# SeniorDesign_PowerBoard_Rev3.net
KiCad netlist of a schematic drawn in Altium Designer
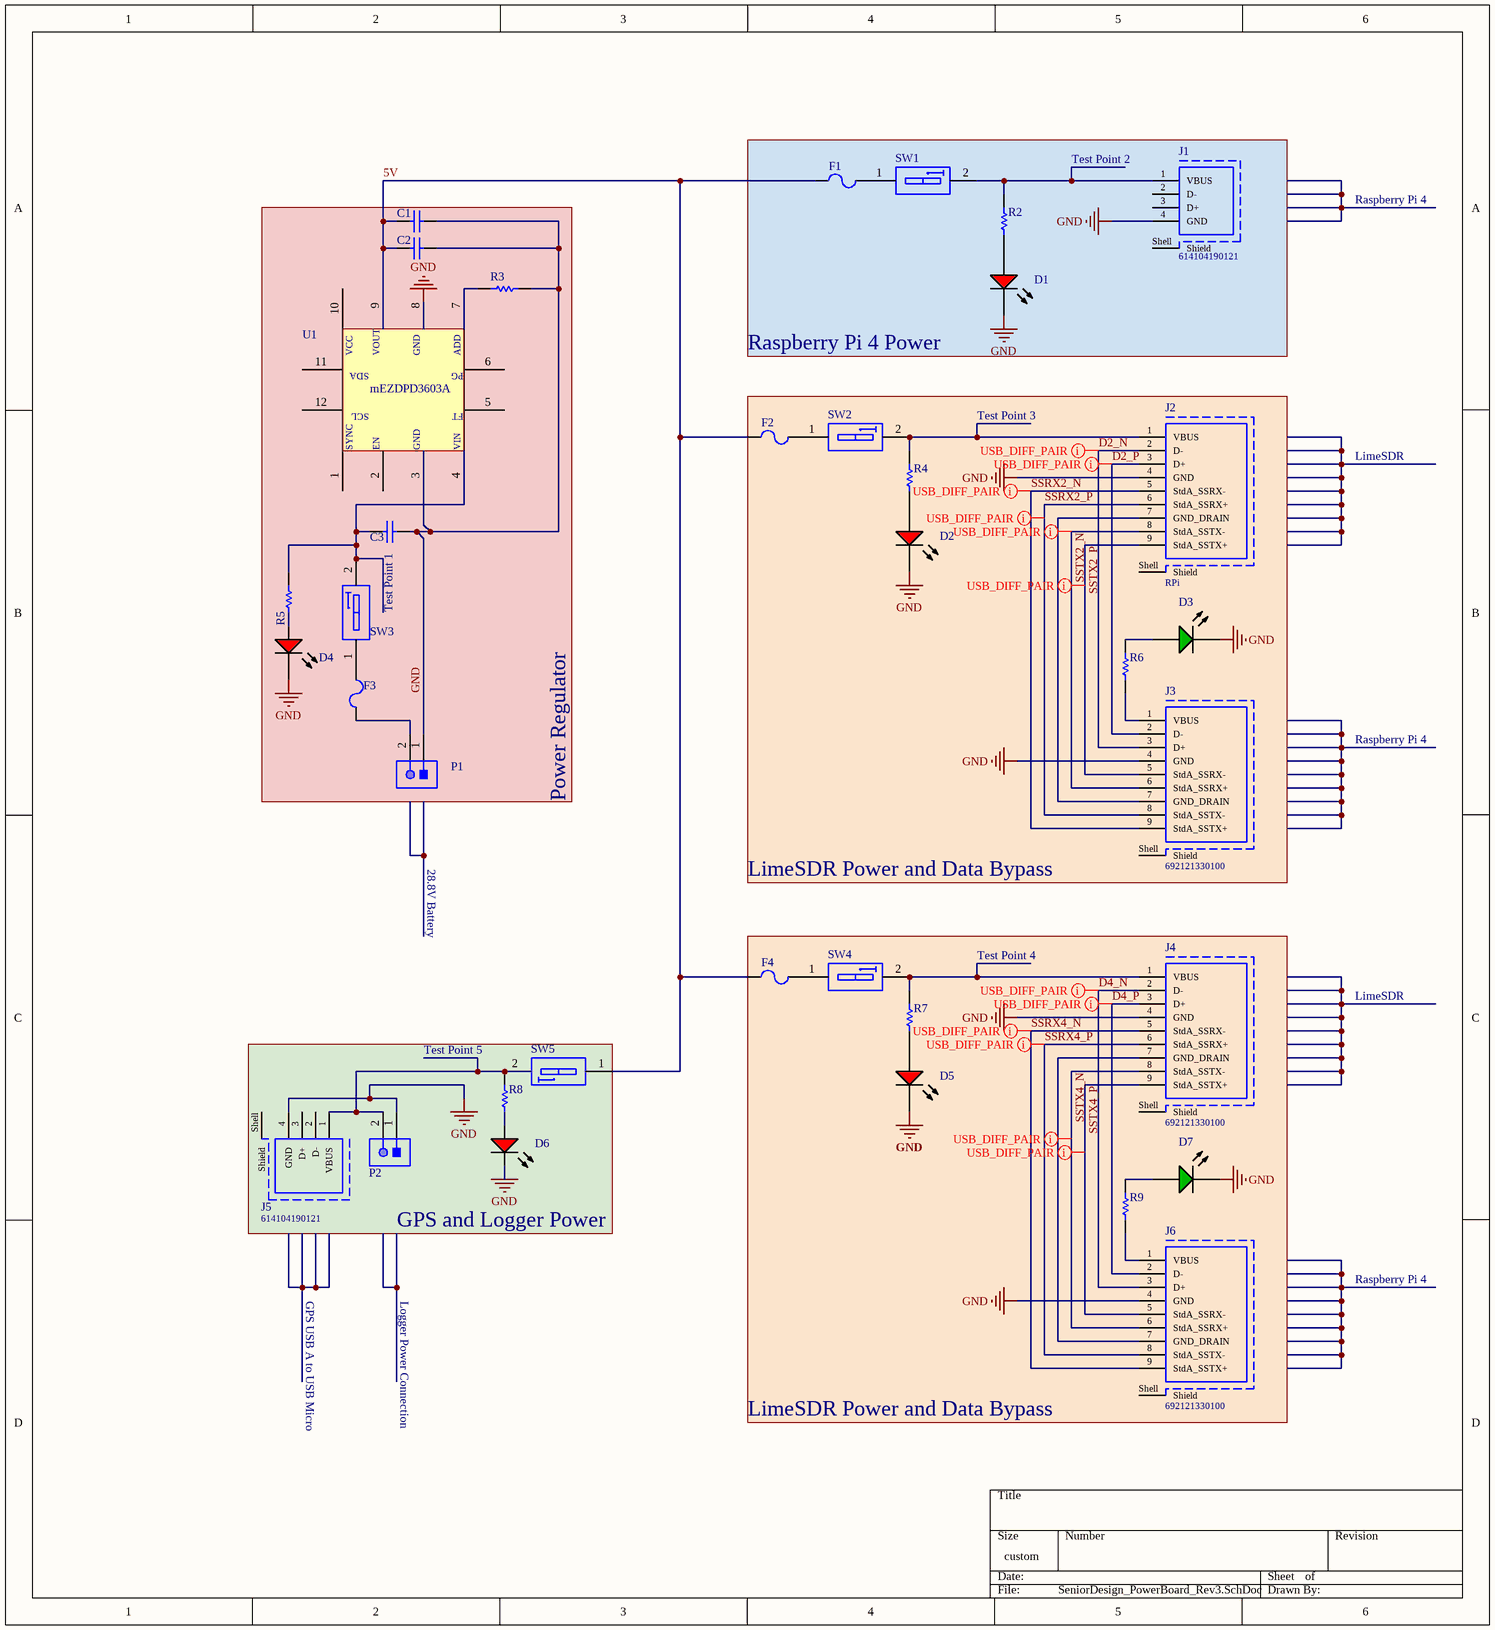
[diagram p0: SeniorDesign_PowerBoard_Rev3.SchDoc]

(export (version "E")
  (design (tool "Eeschema 10.0.6"))
  (components
    (comp (ref "C1")
      (value "GRM188R61A226ME15D")
      (footprint "CAPC1608X100X38LL20T18")
      (description "Chip Capacitor, 22 uF, +/- 20%, 10 V, -55 to 85 degC, 0603 (1608 Metric), RoHS, Tape and Reel")
      (fields (field (name "MANUFACTURER") "Murata") (field (name "TOLERANCE") "20%"))
      (libsource (lib "Altium Content Vault") (part "CAP-NP-2"))
    )
    (comp (ref "C2")
      (value "GRM188R61A226ME15D")
      (footprint "CAPC1608X100X38LL20T18")
      (description "Chip Capacitor, 22 uF, +/- 20%, 10 V, -55 to 85 degC, 0603 (1608 Metric), RoHS, Tape and Reel")
      (fields (field (name "MANUFACTURER") "Murata") (field (name "TOLERANCE") "20%"))
      (libsource (lib "Altium Content Vault") (part "CAP-NP-2"))
    )
    (comp (ref "C3")
      (value "GRM31CR71H475KA12L")
      (footprint "MURA-1206_H_1.8_M")
      (description "CAP, Ceramic, 4.7 uF, 10%, 50 V, 1206, RoHS, Tape and Reel")
      (fields (field (name "MANUFACTURER") "Murata"))
      (libsource (lib "Altium Content Vault") (part "CAP-NP-2"))
    )
    (comp (ref "D1")
      (value "HSMH-C150")
      (footprint "AVAG-HSMX-C150_V")
      (description "LED Uni-Color Red, 65 mW, 25 mA, -40 to 85 degC, 2-Pin SMD, RoHS, Tape and Reel")
      (fields (field (name "MANUFACTURER") "Avago"))
      (libsource (lib "Altium Content Vault") (part "LED-RED-AK-2"))
    )
    (comp (ref "D2")
      (value "HSMH-C150")
      (footprint "AVAG-HSMX-C150_V")
      (description "LED Uni-Color Red, 65 mW, 25 mA, -40 to 85 degC, 2-Pin SMD, RoHS, Tape and Reel")
      (fields (field (name "MANUFACTURER") "Avago"))
      (libsource (lib "Altium Content Vault") (part "LED-RED-AK-2"))
    )
    (comp (ref "D3")
      (value "HSMG-C150")
      (footprint "AVAG-HSMX-C150_V")
      (description "Chip LED, Green, 65 mW, 25 mA, -40 to 85 degC, 2-Pin SMD, RoHS, Tape and Reel")
      (fields (field (name "MANUFACTURER") "Avago"))
      (libsource (lib "Altium Content Vault") (part "LED_GREEN_A1K2-2"))
    )
    (comp (ref "D4")
      (value "HSMH-C150")
      (footprint "AVAG-HSMX-C150_V")
      (description "LED Uni-Color Red, 65 mW, 25 mA, -40 to 85 degC, 2-Pin SMD, RoHS, Tape and Reel")
      (fields (field (name "MANUFACTURER") "Avago"))
      (libsource (lib "Altium Content Vault") (part "LED-RED-AK-2"))
    )
    (comp (ref "D5")
      (value "HSMH-C150")
      (footprint "AVAG-HSMX-C150_V")
      (description "LED Uni-Color Red, 65 mW, 25 mA, -40 to 85 degC, 2-Pin SMD, RoHS, Tape and Reel")
      (fields (field (name "MANUFACTURER") "Avago"))
      (libsource (lib "Altium Content Vault") (part "LED-RED-AK-2"))
    )
    (comp (ref "D6")
      (value "HSMH-C150")
      (footprint "AVAG-HSMX-C150_V")
      (description "LED Uni-Color Red, 65 mW, 25 mA, -40 to 85 degC, 2-Pin SMD, RoHS, Tape and Reel")
      (fields (field (name "MANUFACTURER") "Avago"))
      (libsource (lib "Altium Content Vault") (part "LED-RED-AK-2"))
    )
    (comp (ref "D7")
      (value "HSMG-C150")
      (footprint "AVAG-HSMX-C150_V")
      (description "Chip LED, Green, 65 mW, 25 mA, -40 to 85 degC, 2-Pin SMD, RoHS, Tape and Reel")
      (fields (field (name "MANUFACTURER") "Avago"))
      (libsource (lib "Altium Content Vault") (part "LED_GREEN_A1K2-2"))
    )
    (comp (ref "F1")
      (value "0263.500WRT1L")
      (footprint "LFUS-263-2_V1")
      (fields (field (name "MANUFACTURER") "Littelfuse"))
      (libsource (lib "Altium Content Vault") (part "LFUS-FUSE-2"))
    )
    (comp (ref "F2")
      (value "0263.500WRT1L")
      (footprint "LFUS-263-2_V1")
      (fields (field (name "MANUFACTURER") "Littelfuse"))
      (libsource (lib "Altium Content Vault") (part "LFUS-FUSE-2"))
    )
    (comp (ref "F3")
      (value "0263.500WRT1L")
      (footprint "LFUS-263-2_V1")
      (fields (field (name "MANUFACTURER") "Littelfuse"))
      (libsource (lib "Altium Content Vault") (part "LFUS-FUSE-2"))
    )
    (comp (ref "F4")
      (value "0263.500WRT1L")
      (footprint "LFUS-263-2_V1")
      (fields (field (name "MANUFACTURER") "Littelfuse"))
      (libsource (lib "Altium Content Vault") (part "LFUS-FUSE-2"))
    )
    (comp (ref "J1")
      (value "614104190121")
      (footprint "614104190121")
      (description "USB 2.0 Type A Receptacle WR-COM, Horizontal, THT, Short Type with Clips")
      (fields (field (name "MANUFACTURER") "Wurth Elektronik") (field (name "PUBLISHER") "WurthElektronik"))
      (libsource (lib "Altium Content Vault") (part "WE-USB-4-1SHLD"))
    )
    (comp (ref "J2")
      (value "RPi")
      (footprint "692121330100")
      (description "USB 3.0 Type A Receptacle WR-COM, Reverse Horizontal, SMT / THT, with Clips, with 1.75 mm Offset")
      (fields
        (field (name "MANUFACTURER") "Wurth Elektronik")
        (field (name "PART NUMBER") "692121330100")
        (field (name "PUBLISHER") "WurthElektronik")
      )
      (libsource (lib "Altium Content Vault") (part "WE-USB-9-1SHLD"))
    )
    (comp (ref "J3")
      (value "692121330100")
      (footprint "692121330100")
      (description "USB 3.0 Type A Receptacle WR-COM, Reverse Horizontal, SMT / THT, with Clips, with 1.75 mm Offset")
      (fields (field (name "MANUFACTURER") "Wurth Elektronik") (field (name "PUBLISHER") "WurthElektronik"))
      (libsource (lib "Altium Content Vault") (part "WE-USB-9-1SHLD"))
    )
    (comp (ref "J4")
      (value "692121330100")
      (footprint "692121330100")
      (description "USB 3.0 Type A Receptacle WR-COM, Reverse Horizontal, SMT / THT, with Clips, with 1.75 mm Offset")
      (fields (field (name "MANUFACTURER") "Wurth Elektronik") (field (name "PUBLISHER") "WurthElektronik"))
      (libsource (lib "Altium Content Vault") (part "WE-USB-9-1SHLD"))
    )
    (comp (ref "J5")
      (value "614104190121")
      (footprint "614104190121")
      (description "USB 2.0 Type A Receptacle WR-COM, Horizontal, THT, Short Type with Clips")
      (fields (field (name "MANUFACTURER") "Wurth Elektronik") (field (name "PUBLISHER") "WurthElektronik"))
      (libsource (lib "Altium Content Vault") (part "WE-USB-4-1SHLD"))
    )
    (comp (ref "J6")
      (value "692121330100")
      (footprint "692121330100")
      (description "USB 3.0 Type A Receptacle WR-COM, Reverse Horizontal, SMT / THT, with Clips, with 1.75 mm Offset")
      (fields (field (name "MANUFACTURER") "Wurth Elektronik") (field (name "PUBLISHER") "WurthElektronik"))
      (libsource (lib "Altium Content Vault") (part "WE-USB-9-1SHLD"))
    )
    (comp (ref "P1")
      (value "S2B-PH-K-S(LF)(SN)")
      (footprint "JST-S2B-PH-K-S_V")
      (fields (field (name "TOLERANCE") "20%"))
      (libsource (lib "Altium Content Vault") (part "CN-1P-M-R2"))
    )
    (comp (ref "P2")
      (value "S2B-PH-K-S(LF)(SN)")
      (footprint "JST-S2B-PH-K-S_V")
      (fields (field (name "TOLERANCE") "20%"))
      (libsource (lib "Altium Content Vault") (part "CN-1P-M-R2"))
    )
    (comp (ref "R2")
      (value "CRCW0402150RFKED")
      (footprint "RESC1005X40X25LL05T05")
      (fields (field (name "MANUFACTURER") "Vishay Dale"))
      (libsource (lib "Altium Content Vault") (part "RES"))
    )
    (comp (ref "R3")
      (value "ADD")
      (footprint "RESC2013X50X30LL20T20")
      (fields (field (name "MANUFACTURER") "Vishay Dale") (field (name "PART NUMBER") "CRCW08050000Z0EA"))
      (libsource (lib "Altium Content Vault") (part "RES"))
    )
    (comp (ref "R4")
      (value "CRCW0402150RFKED")
      (footprint "RESC1005X40X25LL05T05")
      (fields (field (name "MANUFACTURER") "Vishay Dale"))
      (libsource (lib "Altium Content Vault") (part "RES"))
    )
    (comp (ref "R5")
      (value "ERJ-8ENF1501V")
      (footprint "RESC3216X70X50LL05T20")
      (description "1k5 Ohm")
      (fields (field (name "MANUFACTURER") "Panasonic"))
      (libsource (lib "Altium Content Vault") (part "RES"))
    )
    (comp (ref "R6")
      (value "CRCW0402150RFKED")
      (footprint "RESC1005X40X25LL05T05")
      (fields (field (name "MANUFACTURER") "Vishay Dale"))
      (libsource (lib "Altium Content Vault") (part "RES"))
    )
    (comp (ref "R7")
      (value "CRCW0402150RFKED")
      (footprint "RESC1005X40X25LL05T05")
      (fields (field (name "MANUFACTURER") "Vishay Dale"))
      (libsource (lib "Altium Content Vault") (part "RES"))
    )
    (comp (ref "R8")
      (value "CRCW0402150RFKED")
      (footprint "RESC1005X40X25LL05T05")
      (fields (field (name "MANUFACTURER") "Vishay Dale"))
      (libsource (lib "Altium Content Vault") (part "RES"))
    )
    (comp (ref "R9")
      (value "CRCW0402150RFKED")
      (footprint "RESC1005X40X25LL05T05")
      (fields (field (name "MANUFACTURER") "Vishay Dale"))
      (libsource (lib "Altium Content Vault") (part "RES"))
    )
    (comp (ref "SW1")
      (value "418121160801")
      (footprint "418121160801")
      (description "WS-DISV 2.54 mm small compact SMD Dip Switch with top tape")
      (fields (field (name "MANUFACTURER") "Wuerth Elektronik"))
      (libsource (lib "Altium Content Vault") (part "WE-DIP-SW-2"))
    )
    (comp (ref "SW2")
      (value "418121160801")
      (footprint "418121160801")
      (description "WS-DISV 2.54 mm small compact SMD Dip Switch with top tape")
      (fields (field (name "MANUFACTURER") "Wuerth Elektronik"))
      (libsource (lib "Altium Content Vault") (part "WE-DIP-SW-2"))
    )
    (comp (ref "SW3")
      (value "418121160801")
      (footprint "418121160801")
      (description "WS-DISV 2.54 mm small compact SMD Dip Switch with top tape")
      (fields (field (name "MANUFACTURER") "Wuerth Elektronik"))
      (libsource (lib "Altium Content Vault") (part "WE-DIP-SW-2"))
    )
    (comp (ref "SW4")
      (value "418121160801")
      (footprint "418121160801")
      (description "WS-DISV 2.54 mm small compact SMD Dip Switch with top tape")
      (fields (field (name "MANUFACTURER") "Wuerth Elektronik"))
      (libsource (lib "Altium Content Vault") (part "WE-DIP-SW-2"))
    )
    (comp (ref "SW5")
      (value "418121160801")
      (footprint "418121160801")
      (description "WS-DISV 2.54 mm small compact SMD Dip Switch with top tape")
      (fields (field (name "MANUFACTURER") "Wuerth Elektronik"))
      (libsource (lib "Altium Content Vault") (part "WE-DIP-SW-2"))
    )
    (comp (ref "U1")
      (value "DC/DC Converter")
      (footprint "mEZDPD3603A")
      (libsource (lib "SeniorDesign_PowerBoard") (part "DC/DC Converter"))
    )
  )
  (nets
    (net (code "1") (name "/5V") (class "Default")
      (node (ref "C1") (pin "2") (pinfunction "2_2") (pintype "passive"))
      (node (ref "C2") (pin "2") (pinfunction "2_2") (pintype "passive"))
      (node (ref "F1") (pin "2") (pinfunction "2_2") (pintype "passive"))
      (node (ref "F2") (pin "2") (pinfunction "2_2") (pintype "passive"))
      (node (ref "F4") (pin "2") (pinfunction "2_2") (pintype "passive"))
      (node (ref "SW5") (pin "1") (pinfunction "1_1") (pintype "passive"))
      (node (ref "U1") (pin "9") (pinfunction "VOUT_9") (pintype "passive"))
    )
    (net (code "2") (name "/D2_N") (class "Default")
      (node (ref "J2") (pin "2") (pinfunction "D-_2") (pintype "passive"))
      (node (ref "J3") (pin "3") (pinfunction "D+_3") (pintype "passive"))
    )
    (net (code "3") (name "/D2_P") (class "Default")
      (node (ref "J2") (pin "3") (pinfunction "D+_3") (pintype "passive"))
      (node (ref "J3") (pin "2") (pinfunction "D-_2") (pintype "passive"))
    )
    (net (code "4") (name "/D4_N") (class "Default")
      (node (ref "J4") (pin "2") (pinfunction "D-_2") (pintype "passive"))
      (node (ref "J6") (pin "3") (pinfunction "D+_3") (pintype "passive"))
    )
    (net (code "5") (name "/D4_P") (class "Default")
      (node (ref "J4") (pin "3") (pinfunction "D+_3") (pintype "passive"))
      (node (ref "J6") (pin "2") (pinfunction "D-_2") (pintype "passive"))
    )
    (net (code "6") (name "/SSRX2_N") (class "Default")
      (node (ref "J2") (pin "5") (pinfunction "StdA_SSRX-_5") (pintype "passive"))
      (node (ref "J3") (pin "9") (pinfunction "StdA_SSTX+_9") (pintype "passive"))
    )
    (net (code "7") (name "/SSRX2_P") (class "Default")
      (node (ref "J2") (pin "6") (pinfunction "StdA_SSRX+_6") (pintype "passive"))
      (node (ref "J3") (pin "8") (pinfunction "StdA_SSTX-_8") (pintype "passive"))
    )
    (net (code "8") (name "/SSRX4_N") (class "Default")
      (node (ref "J4") (pin "5") (pinfunction "StdA_SSRX-_5") (pintype "passive"))
      (node (ref "J6") (pin "9") (pinfunction "StdA_SSTX+_9") (pintype "passive"))
    )
    (net (code "9") (name "/SSRX4_P") (class "Default")
      (node (ref "J4") (pin "6") (pinfunction "StdA_SSRX+_6") (pintype "passive"))
      (node (ref "J6") (pin "8") (pinfunction "StdA_SSTX-_8") (pintype "passive"))
    )
    (net (code "10") (name "/SSTX2_N") (class "Default")
      (node (ref "J2") (pin "8") (pinfunction "StdA_SSTX-_8") (pintype "passive"))
      (node (ref "J3") (pin "6") (pinfunction "StdA_SSRX+_6") (pintype "passive"))
    )
    (net (code "11") (name "/SSTX2_P") (class "Default")
      (node (ref "J2") (pin "9") (pinfunction "StdA_SSTX+_9") (pintype "passive"))
      (node (ref "J3") (pin "5") (pinfunction "StdA_SSRX-_5") (pintype "passive"))
    )
    (net (code "12") (name "/SSTX4_N") (class "Default")
      (node (ref "J4") (pin "8") (pinfunction "StdA_SSTX-_8") (pintype "passive"))
      (node (ref "J6") (pin "6") (pinfunction "StdA_SSRX+_6") (pintype "passive"))
    )
    (net (code "13") (name "/SSTX4_P") (class "Default")
      (node (ref "J4") (pin "9") (pinfunction "StdA_SSTX+_9") (pintype "passive"))
      (node (ref "J6") (pin "5") (pinfunction "StdA_SSRX-_5") (pintype "passive"))
    )
    (net (code "14") (name "GND") (class "Default")
      (node (ref "C1") (pin "1") (pinfunction "1_1") (pintype "passive"))
      (node (ref "C2") (pin "1") (pinfunction "1_1") (pintype "passive"))
      (node (ref "C3") (pin "1") (pinfunction "1_1") (pintype "passive"))
      (node (ref "D1") (pin "2") (pinfunction "K_2") (pintype "passive"))
      (node (ref "D2") (pin "2") (pinfunction "K_2") (pintype "passive"))
      (node (ref "D3") (pin "2") (pinfunction "K_2") (pintype "passive"))
      (node (ref "D4") (pin "2") (pinfunction "K_2") (pintype "passive"))
      (node (ref "D5") (pin "2") (pinfunction "K_2") (pintype "passive"))
      (node (ref "D6") (pin "2") (pinfunction "K_2") (pintype "passive"))
      (node (ref "D7") (pin "2") (pinfunction "K_2") (pintype "passive"))
      (node (ref "J1") (pin "4") (pinfunction "GND_4") (pintype "passive"))
      (node (ref "J2") (pin "4") (pinfunction "GND_4") (pintype "passive"))
      (node (ref "J3") (pin "4") (pinfunction "GND_4") (pintype "passive"))
      (node (ref "J4") (pin "4") (pinfunction "GND_4") (pintype "passive"))
      (node (ref "J5") (pin "4") (pinfunction "GND_4") (pintype "passive"))
      (node (ref "J6") (pin "4") (pinfunction "GND_4") (pintype "passive"))
      (node (ref "P1") (pin "1") (pinfunction "1_1") (pintype "passive"))
      (node (ref "P2") (pin "1") (pinfunction "1_1") (pintype "passive"))
      (node (ref "R3") (pin "1") (pinfunction "1_1") (pintype "passive"))
      (node (ref "U1") (pin "3") (pinfunction "GND_3") (pintype "passive"))
      (node (ref "U1") (pin "8") (pinfunction "GND_8") (pintype "passive"))
    )
    (net (code "15") (name "Net-(D1-A)") (class "Default")
      (node (ref "D1") (pin "1") (pinfunction "A_1") (pintype "passive"))
      (node (ref "R2") (pin "1") (pinfunction "1_1") (pintype "passive"))
    )
    (net (code "16") (name "Net-(D2-A)") (class "Default")
      (node (ref "D2") (pin "1") (pinfunction "A_1") (pintype "passive"))
      (node (ref "R4") (pin "1") (pinfunction "1_1") (pintype "passive"))
    )
    (net (code "17") (name "Net-(D3-A)") (class "Default")
      (node (ref "D3") (pin "1") (pinfunction "A_1") (pintype "passive"))
      (node (ref "R6") (pin "2") (pinfunction "2_2") (pintype "passive"))
    )
    (net (code "18") (name "Net-(D4-A)") (class "Default")
      (node (ref "D4") (pin "1") (pinfunction "A_1") (pintype "passive"))
      (node (ref "R5") (pin "1") (pinfunction "1_1") (pintype "passive"))
    )
    (net (code "19") (name "Net-(D5-A)") (class "Default")
      (node (ref "D5") (pin "1") (pinfunction "A_1") (pintype "passive"))
      (node (ref "R7") (pin "1") (pinfunction "1_1") (pintype "passive"))
    )
    (net (code "20") (name "Net-(D6-A)") (class "Default")
      (node (ref "D6") (pin "1") (pinfunction "A_1") (pintype "passive"))
      (node (ref "R8") (pin "1") (pinfunction "1_1") (pintype "passive"))
    )
    (net (code "21") (name "Net-(D7-A)") (class "Default")
      (node (ref "D7") (pin "1") (pinfunction "A_1") (pintype "passive"))
      (node (ref "R9") (pin "2") (pinfunction "2_2") (pintype "passive"))
    )
    (net (code "22") (name "Net-(F1-Pad1)") (class "Default")
      (node (ref "F1") (pin "1") (pinfunction "1_1") (pintype "passive"))
      (node (ref "SW1") (pin "1") (pinfunction "1_1") (pintype "passive"))
    )
    (net (code "23") (name "Net-(F2-Pad1)") (class "Default")
      (node (ref "F2") (pin "1") (pinfunction "1_1") (pintype "passive"))
      (node (ref "SW2") (pin "1") (pinfunction "1_1") (pintype "passive"))
    )
    (net (code "24") (name "Net-(F3-Pad1)") (class "Default")
      (node (ref "F3") (pin "1") (pinfunction "1_1") (pintype "passive"))
      (node (ref "P1") (pin "2") (pinfunction "2_2") (pintype "passive"))
    )
    (net (code "25") (name "Net-(F3-Pad2)") (class "Default")
      (node (ref "F3") (pin "2") (pinfunction "2_2") (pintype "passive"))
      (node (ref "SW3") (pin "1") (pinfunction "1_1") (pintype "passive"))
    )
    (net (code "26") (name "Net-(F4-Pad1)") (class "Default")
      (node (ref "F4") (pin "1") (pinfunction "1_1") (pintype "passive"))
      (node (ref "SW4") (pin "1") (pinfunction "1_1") (pintype "passive"))
    )
    (net (code "27") (name "Net-(J1-VBUS)") (class "Default")
      (node (ref "J1") (pin "1") (pinfunction "VBUS_1") (pintype "passive"))
      (node (ref "R2") (pin "2") (pinfunction "2_2") (pintype "passive"))
      (node (ref "SW1") (pin "2") (pinfunction "2_2") (pintype "passive"))
    )
    (net (code "28") (name "Net-(J2-GND_DRAIN)") (class "Default")
      (node (ref "J2") (pin "7") (pinfunction "GND_DRAIN_7") (pintype "passive"))
      (node (ref "J3") (pin "7") (pinfunction "GND_DRAIN_7") (pintype "passive"))
    )
    (net (code "29") (name "Net-(J2-VBUS)") (class "Default")
      (node (ref "J2") (pin "1") (pinfunction "VBUS_1") (pintype "passive"))
      (node (ref "R4") (pin "2") (pinfunction "2_2") (pintype "passive"))
      (node (ref "SW2") (pin "2") (pinfunction "2_2") (pintype "passive"))
    )
    (net (code "30") (name "Net-(J3-VBUS)") (class "Default")
      (node (ref "J3") (pin "1") (pinfunction "VBUS_1") (pintype "passive"))
      (node (ref "R6") (pin "1") (pinfunction "1_1") (pintype "passive"))
    )
    (net (code "31") (name "Net-(J4-GND_DRAIN)") (class "Default")
      (node (ref "J4") (pin "7") (pinfunction "GND_DRAIN_7") (pintype "passive"))
      (node (ref "J6") (pin "7") (pinfunction "GND_DRAIN_7") (pintype "passive"))
    )
    (net (code "32") (name "Net-(J4-VBUS)") (class "Default")
      (node (ref "J4") (pin "1") (pinfunction "VBUS_1") (pintype "passive"))
      (node (ref "R7") (pin "2") (pinfunction "2_2") (pintype "passive"))
      (node (ref "SW4") (pin "2") (pinfunction "2_2") (pintype "passive"))
    )
    (net (code "33") (name "Net-(J5-VBUS)") (class "Default")
      (node (ref "J5") (pin "1") (pinfunction "VBUS_1") (pintype "passive"))
      (node (ref "P2") (pin "2") (pinfunction "2_2") (pintype "passive"))
      (node (ref "R8") (pin "2") (pinfunction "2_2") (pintype "passive"))
      (node (ref "SW5") (pin "2") (pinfunction "2_2") (pintype "passive"))
    )
    (net (code "34") (name "Net-(J6-VBUS)") (class "Default")
      (node (ref "J6") (pin "1") (pinfunction "VBUS_1") (pintype "passive"))
      (node (ref "R9") (pin "1") (pinfunction "1_1") (pintype "passive"))
    )
    (net (code "35") (name "Net-(U1-ADD)") (class "Default")
      (node (ref "R3") (pin "2") (pinfunction "2_2") (pintype "passive"))
      (node (ref "U1") (pin "7") (pinfunction "ADD_7") (pintype "passive"))
    )
    (net (code "36") (name "Net-(U1-VIN)") (class "Default")
      (node (ref "C3") (pin "2") (pinfunction "2_2") (pintype "passive"))
      (node (ref "R5") (pin "2") (pinfunction "2_2") (pintype "passive"))
      (node (ref "SW3") (pin "2") (pinfunction "2_2") (pintype "passive"))
      (node (ref "U1") (pin "4") (pinfunction "VIN_4") (pintype "passive"))
    )
    (net (code "37") (name "unconnected-(J1-D+-Pad3)") (class "Default")
      (node (ref "J1") (pin "3") (pinfunction "D+_3") (pintype "passive"))
    )
    (net (code "38") (name "unconnected-(J1-D--Pad2)") (class "Default")
      (node (ref "J1") (pin "2") (pinfunction "D-_2") (pintype "passive"))
    )
    (net (code "39") (name "unconnected-(J1-Shield-PadShell)") (class "Default")
      (node (ref "J1") (pin "Shell") (pinfunction "Shield_Shell") (pintype "passive"))
    )
    (net (code "40") (name "unconnected-(J2-Shield-PadShell)") (class "Default")
      (node (ref "J2") (pin "Shell") (pinfunction "Shield_Shell") (pintype "passive"))
    )
    (net (code "41") (name "unconnected-(J3-Shield-PadShell)") (class "Default")
      (node (ref "J3") (pin "Shell") (pinfunction "Shield_Shell") (pintype "passive"))
    )
    (net (code "42") (name "unconnected-(J4-Shield-PadShell)") (class "Default")
      (node (ref "J4") (pin "Shell") (pinfunction "Shield_Shell") (pintype "passive"))
    )
    (net (code "43") (name "unconnected-(J5-D+-Pad3)") (class "Default")
      (node (ref "J5") (pin "3") (pinfunction "D+_3") (pintype "passive"))
    )
    (net (code "44") (name "unconnected-(J5-D--Pad2)") (class "Default")
      (node (ref "J5") (pin "2") (pinfunction "D-_2") (pintype "passive"))
    )
    (net (code "45") (name "unconnected-(J5-Shield-PadShell)") (class "Default")
      (node (ref "J5") (pin "Shell") (pinfunction "Shield_Shell") (pintype "passive"))
    )
    (net (code "46") (name "unconnected-(J6-Shield-PadShell)") (class "Default")
      (node (ref "J6") (pin "Shell") (pinfunction "Shield_Shell") (pintype "passive"))
    )
    (net (code "47") (name "unconnected-(U1-EN-Pad2)") (class "Default")
      (node (ref "U1") (pin "2") (pinfunction "EN_2") (pintype "passive"))
    )
    (net (code "48") (name "unconnected-(U1-FT-Pad5)") (class "Default")
      (node (ref "U1") (pin "5") (pinfunction "FT_5") (pintype "passive"))
    )
    (net (code "49") (name "unconnected-(U1-PG-Pad6)") (class "Default")
      (node (ref "U1") (pin "6") (pinfunction "PG_6") (pintype "passive"))
    )
    (net (code "50") (name "unconnected-(U1-SCL-Pad12)") (class "Default")
      (node (ref "U1") (pin "12") (pinfunction "SCL_12") (pintype "passive"))
    )
    (net (code "51") (name "unconnected-(U1-SDA-Pad11)") (class "Default")
      (node (ref "U1") (pin "11") (pinfunction "SDA_11") (pintype "passive"))
    )
    (net (code "52") (name "unconnected-(U1-VCC-Pad10)") (class "Default")
      (node (ref "U1") (pin "10") (pinfunction "VCC_10") (pintype "passive"))
    )
    (net (code "53") (name "unconnected-(U1-_SYNC-Pad1)") (class "Default")
      (node (ref "U1") (pin "1") (pinfunction "_SYNC_1") (pintype "passive"))
    )
  )
)
